# Power_Card.net
KiCad netlist of a schematic drawn in Altium Designer
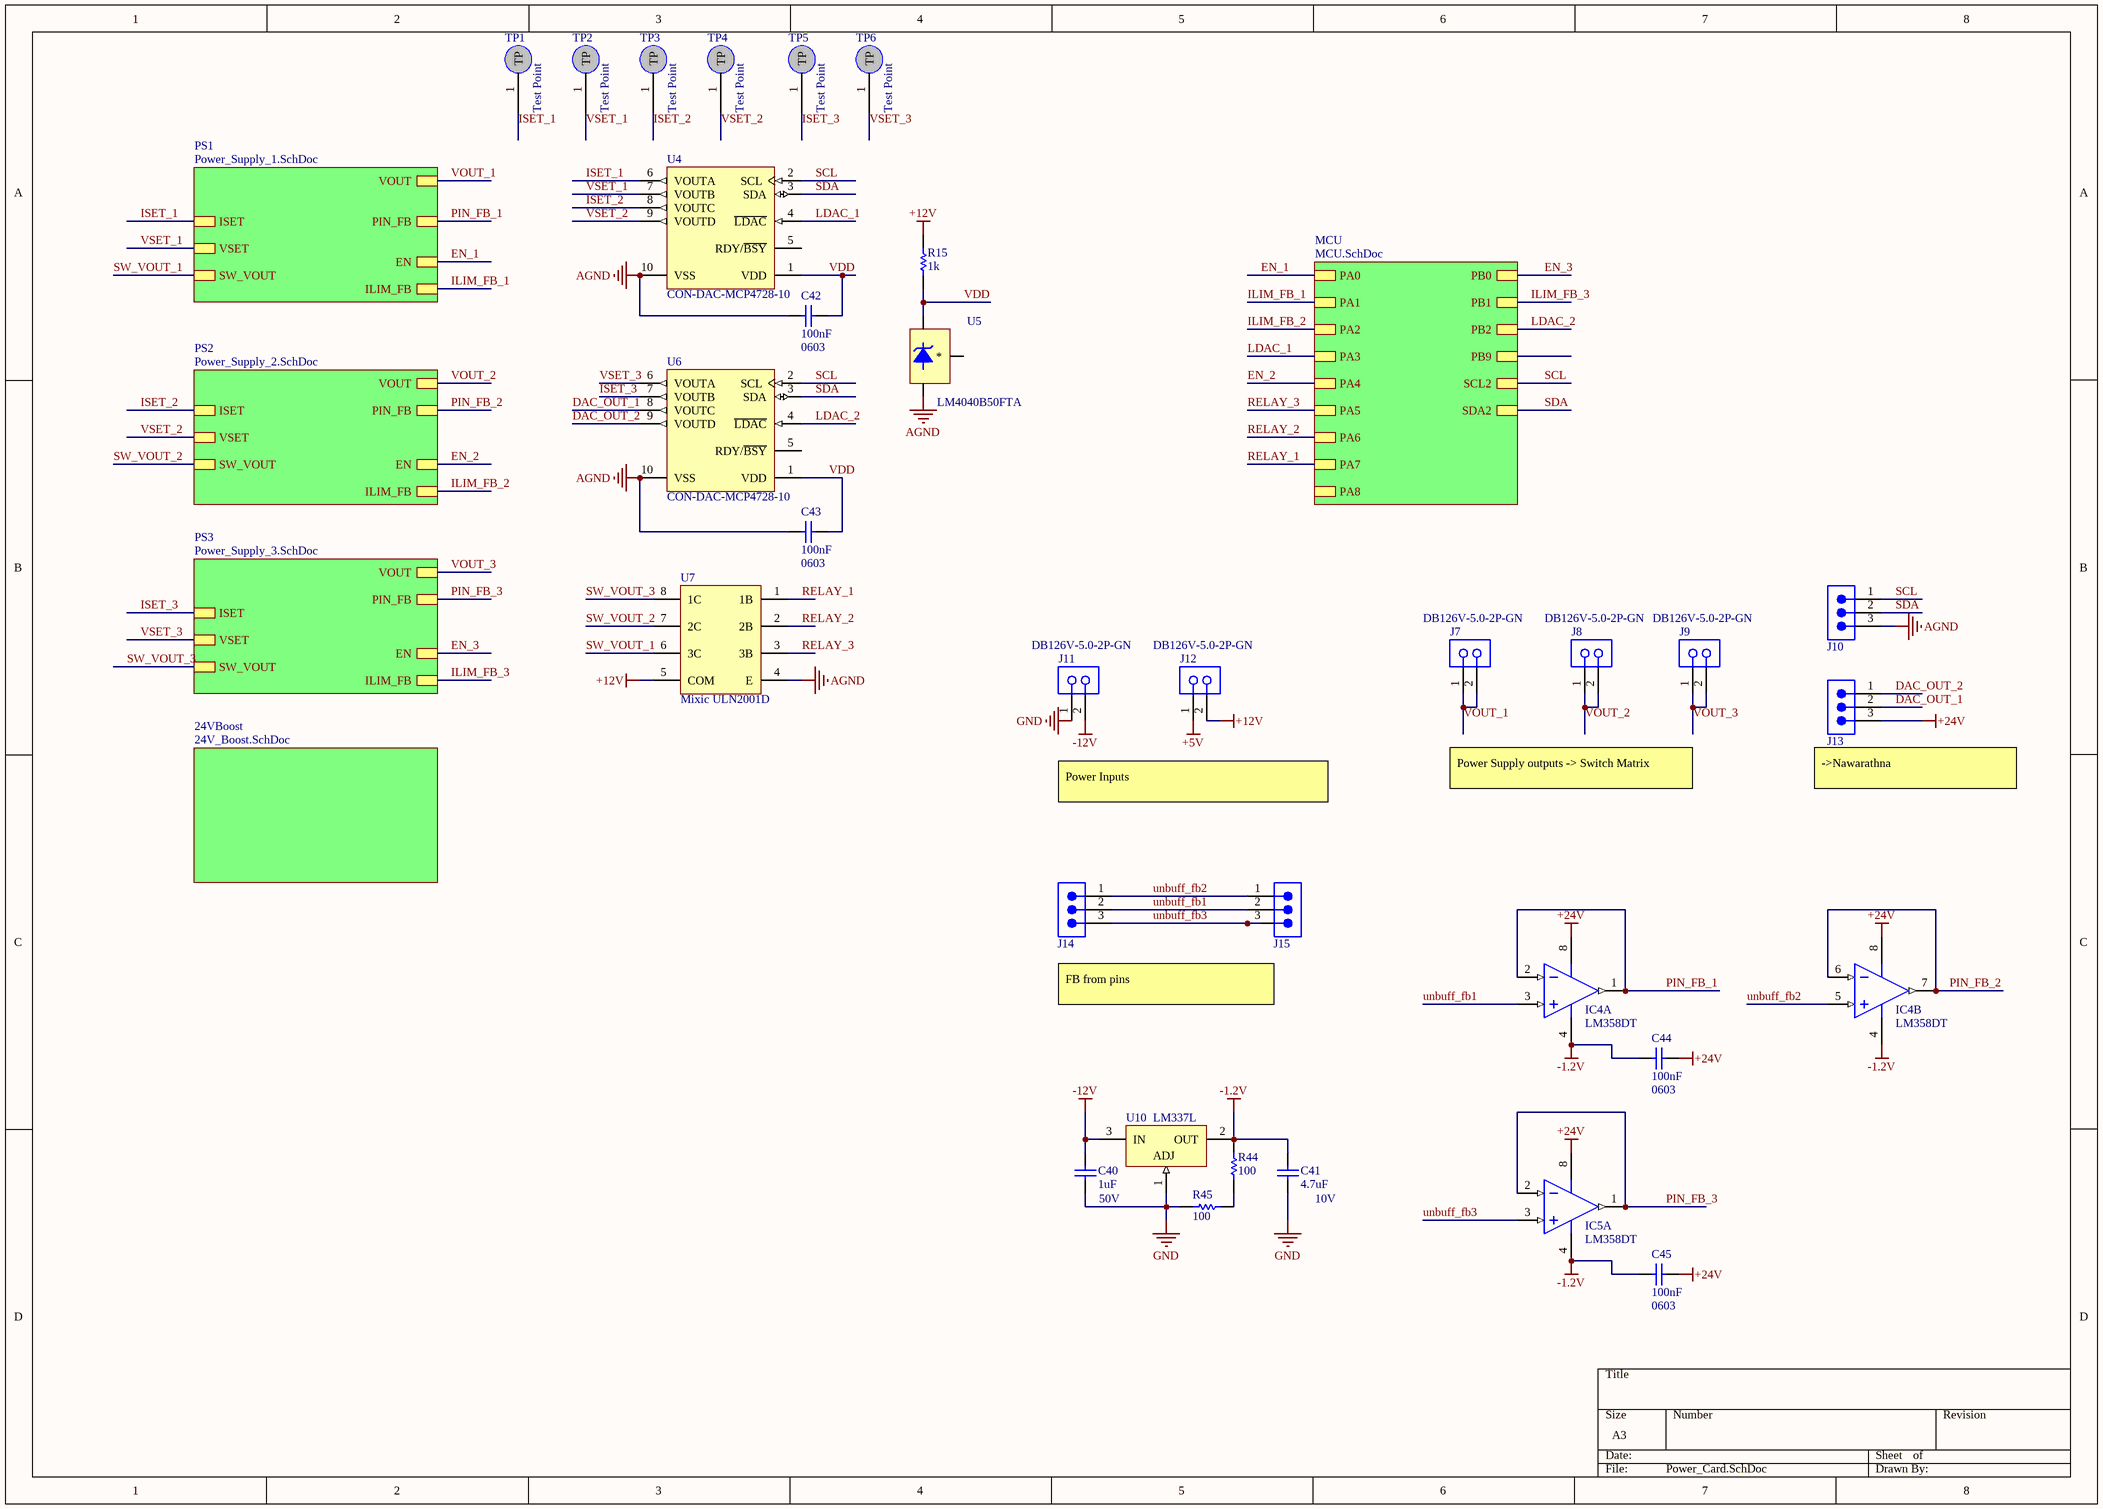
[diagram p0: Power_Card.SchDoc]

(export (version "E")
  (design (tool "Eeschema 10.0.6"))
  (components
    (comp (ref "C40")
      (value "1uF")
      (footprint "CAPC1608X09N")
      (description "0603 10 nF 50 V ± 10% Tolerance X7R Surface Mount Multilayer Ceramic Capacitor")
      (fields
        (field (name "VOLTAGE-RATED") "50V")
        (field (name "MANUFACTURE PART NUMBER") "CL21B105KBFNNNE")
        (field (name "MANUFACTURER") "Samsung Electro-Mechanics")
      )
      (libsource (lib "Current_sence_unit") (part "CMP-2f55e5122ad9f092-5"))
    )
    (comp (ref "C41")
      (value "4.7uF")
      (footprint "CAPC1608X09N")
      (description "0603 10 nF 50 V ± 10% Tolerance X7R Surface Mount Multilayer Ceramic Capacitor")
      (fields
        (field (name "VOLTAGE-RATED") "10V")
        (field (name "MANUFACTURE PART NUMBER") "CL10A475KP8NNNC")
        (field (name "MANUFACTURER") "Samsung Electro-Mechanics")
      )
      (libsource (lib "Current_sence_unit") (part "CMP-2f55e5122ad9f092-5"))
    )
    (comp (ref "C42")
      (value "100nF")
      (footprint "CAPC1608X09N")
      (description "0603 10 nF 50 V ± 10% Tolerance X7R Surface Mount Multilayer Ceramic Capacitor")
      (fields
        (field (name "MANUFACTURE PART NUMBER") "CC0603KRX7R9BB104")
        (field (name "MANUFACTURER") "YAGEO")
        (field (name "PACKAGE / CASE") "0603")
      )
      (libsource (lib "Current_sence_unit") (part "CMP-2f55e5122ad9f092-5"))
    )
    (comp (ref "C43")
      (value "100nF")
      (footprint "CAPC1608X09N")
      (description "0603 10 nF 50 V ± 10% Tolerance X7R Surface Mount Multilayer Ceramic Capacitor")
      (fields
        (field (name "MANUFACTURE PART NUMBER") "CC0603KRX7R9BB104")
        (field (name "MANUFACTURER") "YAGEO")
        (field (name "PACKAGE / CASE") "0603")
      )
      (libsource (lib "Current_sence_unit") (part "CMP-2f55e5122ad9f092-5"))
    )
    (comp (ref "C44")
      (value "100nF")
      (footprint "CAPC1608X09N")
      (description "0603 10 nF 50 V ± 10% Tolerance X7R Surface Mount Multilayer Ceramic Capacitor")
      (fields
        (field (name "MANUFACTURE PART NUMBER") "CC0603KRX7R9BB104")
        (field (name "MANUFACTURER") "YAGEO")
        (field (name "PACKAGE / CASE") "0603")
      )
      (libsource (lib "Current_sence_unit") (part "CMP-2f55e5122ad9f092-5"))
    )
    (comp (ref "C45")
      (value "100nF")
      (footprint "CAPC1608X09N")
      (description "0603 10 nF 50 V ± 10% Tolerance X7R Surface Mount Multilayer Ceramic Capacitor")
      (fields
        (field (name "MANUFACTURE PART NUMBER") "CC0603KRX7R9BB104")
        (field (name "MANUFACTURER") "YAGEO")
        (field (name "PACKAGE / CASE") "0603")
      )
      (libsource (lib "Current_sence_unit") (part "CMP-2f55e5122ad9f092-5"))
    )
    (comp (ref "IC4")
      (value "LM358DT")
      (footprint "SOIC-OA8_M")
      (description "LM358 Series 30 V 1.1 MHz Low Power Dual Operational Amplifier - SOIC-8")
      (fields (field (name "MANUFACTURER") "STMicroelectronics"))
      (libsource (lib "POWER CARD") (part "CMP-9a3c516d515145fb-3"))
    )
    (comp (ref "IC5")
      (value "LM358DT")
      (footprint "SOIC-OA8_M")
      (description "LM358 Series 30 V 1.1 MHz Low Power Dual Operational Amplifier - SOIC-8")
      (fields (field (name "MANUFACTURER") "STMicroelectronics"))
      (libsource (lib "POWER CARD") (part "CMP-9a3c516d515145fb-3"))
    )
    (comp (ref "J7")
      (value "DB126V-5.0-2P-GN")
      (footprint "PCB-kiok1jlp9o9fcwf1wwvf-1")
      (description "Block, Terminal; 13.5 A; 250 V; 5 mm; 26 to 16 AWG; 2; Screw; Solder; 4 kV; PA")
      (fields (field (name "MANUFACTURER") "DIBO"))
      (libsource (lib "POWER CARD") (part "CMP-7ad9b3d37ed8a51e-5"))
    )
    (comp (ref "J8")
      (value "DB126V-5.0-2P-GN")
      (footprint "PCB-kiok1jlp9o9fcwf1wwvf-1")
      (description "Block, Terminal; 13.5 A; 250 V; 5 mm; 26 to 16 AWG; 2; Screw; Solder; 4 kV; PA")
      (fields (field (name "MANUFACTURER") "DIBO"))
      (libsource (lib "POWER CARD") (part "CMP-7ad9b3d37ed8a51e-5"))
    )
    (comp (ref "J9")
      (value "DB126V-5.0-2P-GN")
      (footprint "PCB-kiok1jlp9o9fcwf1wwvf-1")
      (description "Block, Terminal; 13.5 A; 250 V; 5 mm; 26 to 16 AWG; 2; Screw; Solder; 4 kV; PA")
      (fields (field (name "MANUFACTURER") "DIBO"))
      (libsource (lib "POWER CARD") (part "CMP-7ad9b3d37ed8a51e-5"))
    )
    (comp (ref "J10")
      (value "M20-9990346")
      (footprint "PIN_3x1_STR (2.54mm)")
      (description "HARWIN M20 Series, 2.54mm Pitch 3 Way 1 Row Straight PCB Header, Solder Termination, 3A")
      (libsource (lib "POWER CARD") (part "CMP-1d18d4412a33c2df-10"))
    )
    (comp (ref "J11")
      (value "DB126V-5.0-2P-GN")
      (footprint "PCB-kiok1jlp9o9fcwf1wwvf-1")
      (description "Block, Terminal; 13.5 A; 250 V; 5 mm; 26 to 16 AWG; 2; Screw; Solder; 4 kV; PA")
      (fields (field (name "MANUFACTURER") "DIBO"))
      (libsource (lib "POWER CARD") (part "CMP-7ad9b3d37ed8a51e-5"))
    )
    (comp (ref "J12")
      (value "DB126V-5.0-2P-GN")
      (footprint "PCB-kiok1jlp9o9fcwf1wwvf-1")
      (description "Block, Terminal; 13.5 A; 250 V; 5 mm; 26 to 16 AWG; 2; Screw; Solder; 4 kV; PA")
      (fields (field (name "MANUFACTURER") "DIBO"))
      (libsource (lib "POWER CARD") (part "CMP-7ad9b3d37ed8a51e-5"))
    )
    (comp (ref "J13")
      (value "M20-9990346")
      (footprint "PIN_3x1_STR (2.54mm)")
      (description "HARWIN M20 Series, 2.54mm Pitch 3 Way 1 Row Straight PCB Header, Solder Termination, 3A")
      (libsource (lib "POWER CARD") (part "CMP-1d18d4412a33c2df-10"))
    )
    (comp (ref "J14")
      (value "M20-9990346")
      (footprint "PIN_3x1_STR (2.54mm)")
      (description "HARWIN M20 Series, 2.54mm Pitch 3 Way 1 Row Straight PCB Header, Solder Termination, 3A")
      (libsource (lib "POWER CARD") (part "CMP-1d18d4412a33c2df-10"))
    )
    (comp (ref "J15")
      (value "M20-9990346")
      (footprint "PIN_3x1_STR (2.54mm)")
      (description "HARWIN M20 Series, 2.54mm Pitch 3 Way 1 Row Straight PCB Header, Solder Termination, 3A")
      (libsource (lib "POWER CARD") (part "CMP-1d18d4412a33c2df-10"))
    )
    (comp (ref "R15")
      (value "1k")
      (footprint "gen0603-2")
      (description "Surface Mount Thick Film Resistor, RC Series, 1 kohm, 100 mW, - 1%, 50 V, 0603 [1608 Metric]")
      (fields (field (name "MANUFACTURER") "YAGEO") (field (name "MANUFACTURE PART NUMBER") "RC0603FR-071KL"))
      (libsource (lib "Resistor Capacitor") (part "CMP-1853278-27_16"))
    )
    (comp (ref "R44")
      (value "100")
      (footprint "gen0603-2")
      (description "Surface Mount Thick Film Resistor, RC Series, 1 kohm, 100 mW, - 1%, 50 V, 0603 [1608 Metric]")
      (fields
        (field (name "MANUFACTURER") "UNI-ROYAL(Uniroyal Elec)")
        (field (name "MANUFACTURE PART NUMBER") "0603WAF1000T5E")
      )
      (libsource (lib "POWER CARD") (part "CMP-1853278-27"))
    )
    (comp (ref "R45")
      (value "100")
      (footprint "gen0603-2")
      (description "Surface Mount Thick Film Resistor, RC Series, 1 kohm, 100 mW, - 1%, 50 V, 0603 [1608 Metric]")
      (fields
        (field (name "MANUFACTURER") "UNI-ROYAL(Uniroyal Elec)")
        (field (name "MANUFACTURE PART NUMBER") "0603WAF1000T5E")
      )
      (libsource (lib "POWER CARD") (part "CMP-1853278-27"))
    )
    (comp (ref "TP1")
      (value "Test Point")
      (footprint "PCB-76sf9akqozhr8i1vmz2c-1")
      (description "TP")
      (libsource (lib "POWER CARD") (part "CMP-90rr9i2gqvuy4eydob4k-1"))
    )
    (comp (ref "TP2")
      (value "Test Point")
      (footprint "PCB-76sf9akqozhr8i1vmz2c-1")
      (description "TP")
      (libsource (lib "POWER CARD") (part "CMP-90rr9i2gqvuy4eydob4k-1"))
    )
    (comp (ref "TP3")
      (value "Test Point")
      (footprint "PCB-76sf9akqozhr8i1vmz2c-1")
      (description "TP")
      (libsource (lib "POWER CARD") (part "CMP-90rr9i2gqvuy4eydob4k-1"))
    )
    (comp (ref "TP4")
      (value "Test Point")
      (footprint "PCB-76sf9akqozhr8i1vmz2c-1")
      (description "TP")
      (libsource (lib "POWER CARD") (part "CMP-90rr9i2gqvuy4eydob4k-1"))
    )
    (comp (ref "TP5")
      (value "Test Point")
      (footprint "PCB-76sf9akqozhr8i1vmz2c-1")
      (description "TP")
      (libsource (lib "POWER CARD") (part "CMP-90rr9i2gqvuy4eydob4k-1"))
    )
    (comp (ref "TP6")
      (value "Test Point")
      (footprint "PCB-76sf9akqozhr8i1vmz2c-1")
      (description "TP")
      (libsource (lib "POWER CARD") (part "CMP-90rr9i2gqvuy4eydob4k-1"))
    )
    (comp (ref "U4")
      (value "CON-DAC-MCP4728-10")
      (footprint "PCB-psrfqusngns6snaz1e8o-1")
      (description "MCP4728 Series 4 Ch I2C EEPROM Memory 5.5 V 12-Bit D/A Converter SMT - MSOP-10")
      (fields
        (field (name "MANUFACTURE PART NUMBER") "MCP4728-E/UN")
        (field (name "MANUFACTURER") "Microchip Tech")
      )
      (libsource (lib "POWER CARD") (part "CMP-2294796-6"))
    )
    (comp (ref "U5")
      (value "LM4040B50FTA")
      (footprint "PCB-bxhnyzncanvi69437o7v-1")
      (description "LM4040 Series 5 V ±0.2 % Precision Micropower Shunt Voltage Reference - SOT-23")
      (fields (field (name "MANUFACTURER") "Diodes Incorporated"))
      (libsource (lib "POWER CARD") (part "CMP-ed9925821aa6325e-1"))
    )
    (comp (ref "U6")
      (value "CON-DAC-MCP4728-10")
      (footprint "PCB-psrfqusngns6snaz1e8o-1")
      (description "MCP4728 Series 4 Ch I2C EEPROM Memory 5.5 V 12-Bit D/A Converter SMT - MSOP-10")
      (fields
        (field (name "MANUFACTURE PART NUMBER") "MCP4728-E/UN")
        (field (name "MANUFACTURER") "Microchip Tech")
      )
      (libsource (lib "POWER CARD") (part "CMP-2294796-6"))
    )
    (comp (ref "U7")
      (value "Mixic ULN2001D")
      (footprint "PCB-pxs93rufbf6wijgtyo7d-1")
      (description "Darlington transistor array driver")
      (fields (field (name "MANUFACTURER") "Mixic") (field (name "MANUFACTURE PART NUMBER") "ULN2001D"))
      (libsource (lib "POWER CARD") (part "CMP-uwgrh96kdeedshkgggct-4"))
    )
    (comp (ref "U10")
      (value "LM337L")
      (footprint "Z03A")
      (description "3-Terminal Adjustable Regulator, 3-pin TO-92, Pb-Free")
      (fields
        (field (name "MANUFACTURE PART NUMBER") "LM337LZ/NOPB")
        (field (name "MANUFACTURER") "Texas Instruments")
      )
      (libsource (lib "Current_sence_unit") (part "LM337LZ/NOPB"))
    )
  )
  (nets
    (net (code "1") (name "+5V") (class "Default")
      (node (ref "J12") (pin "1") (pinfunction "1_1") (pintype "passive"))
    )
    (net (code "2") (name "+12V") (class "Default")
      (node (ref "J12") (pin "2") (pinfunction "2_2") (pintype "passive"))
      (node (ref "R15") (pin "2") (pinfunction "2_2") (pintype "passive"))
      (node (ref "U7") (pin "5") (pinfunction "COM_5") (pintype "passive"))
    )
    (net (code "3") (name "+24V") (class "Default")
      (node (ref "C44") (pin "2") (pinfunction "2_2") (pintype "passive"))
      (node (ref "C45") (pin "2") (pinfunction "2_2") (pintype "passive"))
      (node (ref "IC4") (pin "8") (pinfunction "VCC_8") (pintype "power_in"))
      (node (ref "IC5") (pin "8") (pinfunction "VCC_8") (pintype "power_in"))
      (node (ref "J13") (pin "3") (pinfunction "3_3") (pintype "passive"))
    )
    (net (code "4") (name "-1.2V") (class "Default")
      (node (ref "C41") (pin "2") (pinfunction "2_2") (pintype "passive"))
      (node (ref "C44") (pin "1") (pinfunction "1_1") (pintype "passive"))
      (node (ref "C45") (pin "1") (pinfunction "1_1") (pintype "passive"))
      (node (ref "IC4") (pin "4") (pinfunction "VEE/GND_4") (pintype "power_in"))
      (node (ref "IC5") (pin "4") (pinfunction "VEE/GND_4") (pintype "power_in"))
      (node (ref "R44") (pin "1") (pinfunction "1_1") (pintype "passive"))
      (node (ref "U10") (pin "2") (pinfunction "OUT_2") (pintype "power_in"))
    )
    (net (code "5") (name "-12V") (class "Default")
      (node (ref "C40") (pin "2") (pinfunction "2_2") (pintype "passive"))
      (node (ref "J11") (pin "2") (pinfunction "2_2") (pintype "passive"))
      (node (ref "U10") (pin "3") (pinfunction "IN_3") (pintype "power_in"))
    )
    (net (code "6") (name "/DAC_OUT_1") (class "Default")
      (node (ref "J13") (pin "2") (pinfunction "2_2") (pintype "passive"))
      (node (ref "U6") (pin "8") (pinfunction "VOUTC_8") (pintype "output"))
    )
    (net (code "7") (name "/DAC_OUT_2") (class "Default")
      (node (ref "J13") (pin "1") (pinfunction "1_1") (pintype "passive"))
      (node (ref "U6") (pin "9") (pinfunction "VOUTD_9") (pintype "output"))
    )
    (net (code "14") (name "/ISET_1") (class "Default")
      (node (ref "TP1") (pin "1") (pinfunction "TP_1") (pintype "passive"))
      (node (ref "U4") (pin "6") (pinfunction "VOUTA_6") (pintype "output"))
    )
    (net (code "15") (name "/ISET_2") (class "Default")
      (node (ref "TP3") (pin "1") (pinfunction "TP_1") (pintype "passive"))
      (node (ref "U4") (pin "8") (pinfunction "VOUTC_8") (pintype "output"))
    )
    (net (code "16") (name "/ISET_3") (class "Default")
      (node (ref "TP5") (pin "1") (pinfunction "TP_1") (pintype "passive"))
      (node (ref "U6") (pin "7") (pinfunction "VOUTB_7") (pintype "output"))
    )
    (net (code "17") (name "/LDAC_1") (class "Default")
      (node (ref "U4") (pin "4") (pinfunction "~{LDAC}_4") (pintype "input"))
    )
    (net (code "18") (name "/LDAC_2") (class "Default")
      (node (ref "U6") (pin "4") (pinfunction "~{LDAC}_4") (pintype "input"))
    )
    (net (code "21") (name "/PIN_FB_1") (class "Default")
      (node (ref "IC4") (pin "1") (pinfunction "OUTA_1") (pintype "output"))
      (node (ref "IC4") (pin "2") (pinfunction "INA-_2") (pintype "input"))
    )
    (net (code "22") (name "/PIN_FB_2") (class "Default")
      (node (ref "IC4") (pin "6") (pinfunction "INB-_6") (pintype "input"))
      (node (ref "IC4") (pin "7") (pinfunction "OUTB_7") (pintype "output"))
    )
    (net (code "23") (name "/PIN_FB_3") (class "Default")
      (node (ref "IC5") (pin "1") (pinfunction "OUTA_1") (pintype "output"))
      (node (ref "IC5") (pin "2") (pinfunction "INA-_2") (pintype "input"))
    )
    (net (code "24") (name "/RELAY_1") (class "Default")
      (node (ref "U7") (pin "1") (pinfunction "1B_1") (pintype "passive"))
    )
    (net (code "25") (name "/RELAY_2") (class "Default")
      (node (ref "U7") (pin "2") (pinfunction "2B_2") (pintype "passive"))
    )
    (net (code "26") (name "/RELAY_3") (class "Default")
      (node (ref "U7") (pin "3") (pinfunction "3B_3") (pintype "passive"))
    )
    (net (code "27") (name "/SCL") (class "Default")
      (node (ref "J10") (pin "1") (pinfunction "1_1") (pintype "passive"))
      (node (ref "U4") (pin "2") (pinfunction "SCL_2") (pintype "input"))
      (node (ref "U6") (pin "2") (pinfunction "SCL_2") (pintype "input"))
    )
    (net (code "28") (name "/SDA") (class "Default")
      (node (ref "J10") (pin "2") (pinfunction "2_2") (pintype "passive"))
      (node (ref "U4") (pin "3") (pinfunction "SDA_3") (pintype "bidirectional"))
      (node (ref "U6") (pin "3") (pinfunction "SDA_3") (pintype "bidirectional"))
    )
    (net (code "29") (name "/SW_VOUT_1") (class "Default")
      (node (ref "U7") (pin "6") (pinfunction "3C_6") (pintype "passive"))
    )
    (net (code "30") (name "/SW_VOUT_2") (class "Default")
      (node (ref "U7") (pin "7") (pinfunction "2C_7") (pintype "passive"))
    )
    (net (code "31") (name "/SW_VOUT_3") (class "Default")
      (node (ref "U7") (pin "8") (pinfunction "1C_8") (pintype "passive"))
    )
    (net (code "32") (name "/VDD") (class "Default")
      (node (ref "C42") (pin "1") (pinfunction "1_1") (pintype "passive"))
      (node (ref "C43") (pin "2") (pinfunction "2_2") (pintype "passive"))
      (node (ref "R15") (pin "1") (pinfunction "1_1") (pintype "passive"))
      (node (ref "U4") (pin "1") (pinfunction "VDD_1") (pintype "power_in"))
      (node (ref "U5") (pin "3") (pinfunction "+V_3") (pintype "passive"))
      (node (ref "U6") (pin "1") (pinfunction "VDD_1") (pintype "power_in"))
    )
    (net (code "33") (name "/VOUT_1") (class "Default")
      (node (ref "J7") (pin "1") (pinfunction "1_1") (pintype "passive"))
      (node (ref "J7") (pin "2") (pinfunction "2_2") (pintype "passive"))
    )
    (net (code "34") (name "/VOUT_2") (class "Default")
      (node (ref "J8") (pin "1") (pinfunction "1_1") (pintype "passive"))
      (node (ref "J8") (pin "2") (pinfunction "2_2") (pintype "passive"))
    )
    (net (code "35") (name "/VOUT_3") (class "Default")
      (node (ref "J9") (pin "1") (pinfunction "1_1") (pintype "passive"))
      (node (ref "J9") (pin "2") (pinfunction "2_2") (pintype "passive"))
    )
    (net (code "36") (name "/VSET_1") (class "Default")
      (node (ref "TP2") (pin "1") (pinfunction "TP_1") (pintype "passive"))
      (node (ref "U4") (pin "7") (pinfunction "VOUTB_7") (pintype "output"))
    )
    (net (code "37") (name "/VSET_2") (class "Default")
      (node (ref "TP4") (pin "1") (pinfunction "TP_1") (pintype "passive"))
      (node (ref "U4") (pin "9") (pinfunction "VOUTD_9") (pintype "output"))
    )
    (net (code "38") (name "/VSET_3") (class "Default")
      (node (ref "TP6") (pin "1") (pinfunction "TP_1") (pintype "passive"))
      (node (ref "U6") (pin "6") (pinfunction "VOUTA_6") (pintype "output"))
    )
    (net (code "39") (name "/unbuff_fb1") (class "Default")
      (node (ref "IC4") (pin "3") (pinfunction "INA+_3") (pintype "input"))
      (node (ref "J14") (pin "2") (pinfunction "2_2") (pintype "passive"))
      (node (ref "J15") (pin "2") (pinfunction "2_2") (pintype "passive"))
    )
    (net (code "40") (name "/unbuff_fb2") (class "Default")
      (node (ref "IC4") (pin "5") (pinfunction "INB+_5") (pintype "input"))
      (node (ref "J14") (pin "1") (pinfunction "1_1") (pintype "passive"))
      (node (ref "J15") (pin "1") (pinfunction "1_1") (pintype "passive"))
    )
    (net (code "41") (name "/unbuff_fb3") (class "Default")
      (node (ref "IC5") (pin "3") (pinfunction "INA+_3") (pintype "input"))
      (node (ref "J14") (pin "3") (pinfunction "3_3") (pintype "passive"))
      (node (ref "J15") (pin "3") (pinfunction "3_3") (pintype "passive"))
    )
    (net (code "42") (name "AGND") (class "Default")
      (node (ref "C42") (pin "2") (pinfunction "2_2") (pintype "passive"))
      (node (ref "C43") (pin "1") (pinfunction "1_1") (pintype "passive"))
      (node (ref "J10") (pin "3") (pinfunction "3_3") (pintype "passive"))
      (node (ref "U4") (pin "10") (pinfunction "VSS_10") (pintype "power_in"))
      (node (ref "U5") (pin "2") (pinfunction "-V_2") (pintype "passive"))
      (node (ref "U6") (pin "10") (pinfunction "VSS_10") (pintype "power_in"))
      (node (ref "U7") (pin "4") (pinfunction "E_4") (pintype "passive"))
    )
    (net (code "43") (name "GND") (class "Default")
      (node (ref "C40") (pin "1") (pinfunction "1_1") (pintype "passive"))
      (node (ref "C41") (pin "1") (pinfunction "1_1") (pintype "passive"))
      (node (ref "J11") (pin "1") (pinfunction "1_1") (pintype "passive"))
      (node (ref "R45") (pin "2") (pinfunction "2_2") (pintype "passive"))
      (node (ref "U10") (pin "1") (pinfunction "ADJ_1") (pintype "input"))
    )
    (net (code "44") (name "Net-(R44-Pad2)") (class "Default")
      (node (ref "R44") (pin "2") (pinfunction "2_2") (pintype "passive"))
      (node (ref "R45") (pin "1") (pinfunction "1_1") (pintype "passive"))
    )
    (net (code "45") (name "unconnected-(U4-RDY{slash}~{BSY}-Pad5)") (class "Default")
      (node (ref "U4") (pin "5") (pinfunction "RDY/~{BSY}_5") (pintype "open_collector"))
    )
    (net (code "46") (name "unconnected-(U5-*-Pad1)") (class "Default")
      (node (ref "U5") (pin "1") (pinfunction "*_1") (pintype "passive"))
    )
    (net (code "47") (name "unconnected-(U6-RDY{slash}~{BSY}-Pad5)") (class "Default")
      (node (ref "U6") (pin "5") (pinfunction "RDY/~{BSY}_5") (pintype "open_collector"))
    )
  )
)
